# 37V_efuse.net
KiCad netlist of a schematic drawn in Altium Designer
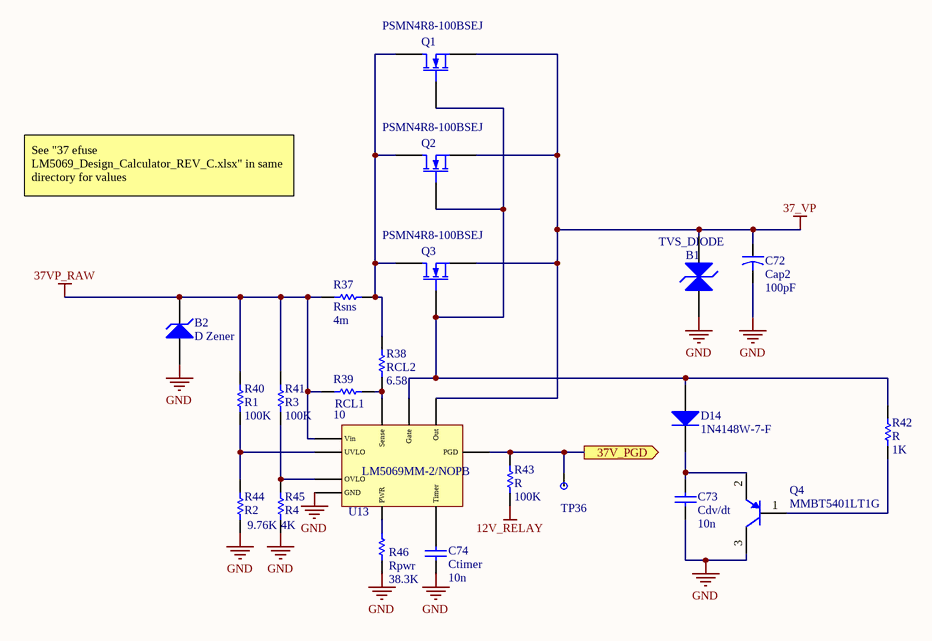
[diagram p0: 37V_efuse.SchDoc]

(export (version "E")
  (design (tool "Eeschema 10.0.6"))
  (components
    (comp (ref "B1")
      (value "TVS_DIODE")
      (footprint "SMBJ54A-13-F")
      (description "TVS Diode")
      (fields (field (name "PUBLISHER") "Altium Limited"))
      (libsource (lib "RSX_Diodes") (part "TVS_DIODE"))
    )
    (comp (ref "B2")
      (value "D Zener")
      (footprint "DIODE-0.7")
      (description "Zener Diode")
      (fields (field (name "PUBLISHER") "Altium Limited"))
      (libsource (lib "Miscellaneous Devices") (part "D Zener"))
    )
    (comp (ref "C72")
      (value "Cap2")
      (footprint "CAPR5-4X5")
      (description "Capacitor")
      (fields (field (name "ALTIUM_VALUE") "100pF") (field (name "PUBLISHER") "Altium Limited"))
      (libsource (lib "Miscellaneous Devices") (part "Cap2"))
    )
    (comp (ref "C73")
      (value "Cdv/dt")
      (footprint "RAD-0.3")
      (description "Capacitor")
      (fields (field (name "ALTIUM_VALUE") "10n") (field (name "PUBLISHER") "Altium Limited"))
      (libsource (lib "Miscellaneous Devices") (part "Cap"))
    )
    (comp (ref "C74")
      (value "Ctimer")
      (footprint "RAD-0.3")
      (description "Capacitor")
      (fields (field (name "ALTIUM_VALUE") "10n") (field (name "PUBLISHER") "Altium Limited"))
      (libsource (lib "Miscellaneous Devices") (part "Cap"))
    )
    (comp (ref "D14")
      (value "1N4148W-7-F")
      (footprint "DIOD-SOD123-2_V")
      (description "Fast Switching Diode, 100 V, 0.15 A, -65 to 150 degC, 2-Pin?SOD123, RoHS, Tape and Reel")
      (fields (field (name "MANUFACTURER") "DiodesIncorporated"))
      (libsource (lib "Altium Content Vault") (part "D-AK-2"))
    )
    (comp (ref "Q1")
      (value "PSMN4R8-100BSEJ")
      (footprint "DPAK254P1420X457-3N")
      (description "N-Channel MOSFET")
      (fields (field (name "PUBLISHER") "Altium Limited"))
      (libsource (lib "RSX_ICs") (part "PSMN4R8-100BSEJ"))
    )
    (comp (ref "Q2")
      (value "PSMN4R8-100BSEJ")
      (footprint "DPAK254P1420X457-3N")
      (description "N-Channel MOSFET")
      (fields (field (name "PUBLISHER") "Altium Limited"))
      (libsource (lib "RSX_ICs") (part "PSMN4R8-100BSEJ"))
    )
    (comp (ref "Q3")
      (value "PSMN4R8-100BSEJ")
      (footprint "DPAK254P1420X457-3N")
      (description "N-Channel MOSFET")
      (fields (field (name "PUBLISHER") "Altium Limited"))
      (libsource (lib "RSX_ICs") (part "PSMN4R8-100BSEJ"))
    )
    (comp (ref "Q4")
      (value "MMBT5401LT1G")
      (footprint "ONSC-SOT-23-3-318-08_V")
      (description "High Voltage Transistor, PNP Silicon, 3-Pin SOT-23, Pb-Free, Tape and Reel")
      (fields (field (name "MANUFACTURER") "On Semiconductor"))
      (libsource (lib "Altium Content Vault") (part "ONSC-PNP-B1E2C3-3"))
    )
    (comp (ref "R37")
      (value "Rsns")
      (footprint "RESC1608X06N_0603")
      (description "Resistor")
      (fields (field (name "ALTIUM_VALUE") "4m") (field (name "PUBLISHER") "Altium Limited"))
      (libsource (lib "RSX_Resistors") (part "Res1"))
    )
    (comp (ref "R38")
      (value "RCL2")
      (footprint "RESC1608X06N_0603")
      (description "Resistor")
      (fields (field (name "ALTIUM_VALUE") "6.58") (field (name "PUBLISHER") "Altium Limited"))
      (libsource (lib "RSX_Resistors") (part "Res1"))
    )
    (comp (ref "R39")
      (value "RCL1")
      (footprint "RESC1608X06N_0603")
      (description "Resistor")
      (fields (field (name "ALTIUM_VALUE") "10") (field (name "PUBLISHER") "Altium Limited"))
      (libsource (lib "RSX_Resistors") (part "Res1"))
    )
    (comp (ref "R40")
      (value "R1")
      (footprint "RESC1608X06N_0603")
      (description "Resistor")
      (fields (field (name "ALTIUM_VALUE") "100K") (field (name "PUBLISHER") "Altium Limited"))
      (libsource (lib "RSX_Resistors") (part "Res1"))
    )
    (comp (ref "R41")
      (value "R3")
      (footprint "RESC1608X06N_0603")
      (description "Resistor")
      (fields (field (name "ALTIUM_VALUE") "100K") (field (name "PUBLISHER") "Altium Limited"))
      (libsource (lib "RSX_Resistors") (part "Res1"))
    )
    (comp (ref "R42")
      (value "R")
      (footprint "RESC1608X06N_0603")
      (description "Resistor")
      (fields (field (name "ALTIUM_VALUE") "1K") (field (name "PUBLISHER") "Altium Limited"))
      (libsource (lib "RSX_Resistors") (part "Res1"))
    )
    (comp (ref "R43")
      (value "R")
      (footprint "RESC1608X06N_0603")
      (description "Resistor")
      (fields (field (name "ALTIUM_VALUE") "100K") (field (name "PUBLISHER") "Altium Limited"))
      (libsource (lib "RSX_Resistors") (part "Res1"))
    )
    (comp (ref "R44")
      (value "R2")
      (footprint "RESC1608X06N_0603")
      (description "Resistor")
      (fields (field (name "ALTIUM_VALUE") "9.76K") (field (name "PUBLISHER") "Altium Limited"))
      (libsource (lib "RSX_Resistors") (part "Res1"))
    )
    (comp (ref "R45")
      (value "R4")
      (footprint "RESC1608X06N_0603")
      (description "Resistor")
      (fields (field (name "ALTIUM_VALUE") "4K") (field (name "PUBLISHER") "Altium Limited"))
      (libsource (lib "RSX_Resistors") (part "Res1"))
    )
    (comp (ref "R46")
      (value "Rpwr")
      (footprint "RESC1608X06N_0603")
      (description "Resistor")
      (fields (field (name "ALTIUM_VALUE") "38.3K") (field (name "PUBLISHER") "Altium Limited"))
      (libsource (lib "RSX_Resistors") (part "Res1"))
    )
    (comp (ref "TP36")
      (value "TestPt")
      (footprint "50_MIL_PAD")
      (libsource (lib "RSX_Test_Points") (part "TestPt"))
    )
    (comp (ref "U13")
      (value "LM5069MM-2/NOPB")
      (footprint "TSSOP50P490X110-10N")
      (description "Hot Swap Controller 1-CH 80V N-Channel Positive High Voltage 10-Pin VSSOP T/R")
      (libsource (lib "RSX_ICs") (part "LM5069MM-2/NOPB"))
    )
  )
  (nets
    (net (code "1") (name "/37V_PGD") (class "Default")
      (node (ref "R43") (pin "2") (pinfunction "2_2") (pintype "passive"))
      (node (ref "TP36") (pin "1") (pinfunction "1_1") (pintype "passive"))
      (node (ref "U13") (pin "8") (pinfunction "PGD_8") (pintype "passive"))
    )
    (net (code "2") (name "12V_RELAY") (class "Default")
      (node (ref "R43") (pin "1") (pinfunction "1_1") (pintype "passive"))
    )
    (net (code "3") (name "37VP_RAW") (class "Default")
      (node (ref "B2") (pin "2") (pinfunction "K_2") (pintype "passive"))
      (node (ref "R37") (pin "1") (pinfunction "1_1") (pintype "passive"))
      (node (ref "R39") (pin "1") (pinfunction "1_1") (pintype "passive"))
      (node (ref "R40") (pin "2") (pinfunction "2_2") (pintype "passive"))
      (node (ref "R41") (pin "2") (pinfunction "2_2") (pintype "passive"))
      (node (ref "U13") (pin "2") (pinfunction "Vin_2") (pintype "passive"))
    )
    (net (code "4") (name "37_VP") (class "Default")
      (node (ref "B1") (pin "2") (pinfunction "K_2") (pintype "passive"))
      (node (ref "C72") (pin "1") (pinfunction "1_1") (pintype "passive"))
      (node (ref "Q1") (pin "3") (pinfunction "S_3") (pintype "passive"))
      (node (ref "Q2") (pin "3") (pinfunction "S_3") (pintype "passive"))
      (node (ref "Q3") (pin "3") (pinfunction "S_3") (pintype "passive"))
      (node (ref "U13") (pin "9") (pinfunction "Out_9") (pintype "passive"))
    )
    (net (code "5") (name "GND") (class "Default")
      (node (ref "B1") (pin "1") (pinfunction "A_1") (pintype "passive"))
      (node (ref "B2") (pin "1") (pinfunction "A_1") (pintype "passive"))
      (node (ref "C72") (pin "2") (pinfunction "2_2") (pintype "passive"))
      (node (ref "C73") (pin "2") (pinfunction "2_2") (pintype "passive"))
      (node (ref "C74") (pin "1") (pinfunction "1_1") (pintype "passive"))
      (node (ref "Q4") (pin "3") (pinfunction "C_3") (pintype "passive"))
      (node (ref "R44") (pin "1") (pinfunction "1_1") (pintype "passive"))
      (node (ref "R45") (pin "1") (pinfunction "1_1") (pintype "passive"))
      (node (ref "R46") (pin "1") (pinfunction "1_1") (pintype "passive"))
      (node (ref "U13") (pin "5") (pinfunction "GND_5") (pintype "passive"))
    )
    (net (code "6") (name "Net-(D14-A)") (class "Default")
      (node (ref "D14") (pin "1") (pinfunction "A_1") (pintype "passive"))
      (node (ref "Q1") (pin "1") (pinfunction "G_1") (pintype "passive"))
      (node (ref "Q2") (pin "1") (pinfunction "G_1") (pintype "passive"))
      (node (ref "Q3") (pin "1") (pinfunction "G_1") (pintype "passive"))
      (node (ref "R42") (pin "2") (pinfunction "2_2") (pintype "passive"))
      (node (ref "U13") (pin "10") (pinfunction "Gate_10") (pintype "passive"))
    )
    (net (code "7") (name "Net-(D14-K)") (class "Default")
      (node (ref "C73") (pin "1") (pinfunction "1_1") (pintype "passive"))
      (node (ref "D14") (pin "2") (pinfunction "K_2") (pintype "passive"))
      (node (ref "Q4") (pin "2") (pinfunction "E_2") (pintype "passive"))
    )
    (net (code "8") (name "Net-(Q1-D)") (class "Default")
      (node (ref "Q1") (pin "2") (pinfunction "D_2") (pintype "passive"))
      (node (ref "Q2") (pin "2") (pinfunction "D_2") (pintype "passive"))
      (node (ref "Q3") (pin "2") (pinfunction "D_2") (pintype "passive"))
      (node (ref "R37") (pin "2") (pinfunction "2_2") (pintype "passive"))
      (node (ref "R38") (pin "2") (pinfunction "2_2") (pintype "passive"))
    )
    (net (code "9") (name "Net-(Q4-B)") (class "Default")
      (node (ref "Q4") (pin "1") (pinfunction "B_1") (pintype "passive"))
      (node (ref "R42") (pin "1") (pinfunction "1_1") (pintype "passive"))
    )
    (net (code "10") (name "Net-(U13-OVLO)") (class "Default")
      (node (ref "R41") (pin "1") (pinfunction "1_1") (pintype "passive"))
      (node (ref "R45") (pin "2") (pinfunction "2_2") (pintype "passive"))
      (node (ref "U13") (pin "4") (pinfunction "OVLO_4") (pintype "passive"))
    )
    (net (code "11") (name "Net-(U13-PWR)") (class "Default")
      (node (ref "R46") (pin "2") (pinfunction "2_2") (pintype "passive"))
      (node (ref "U13") (pin "7") (pinfunction "PWR_7") (pintype "passive"))
    )
    (net (code "12") (name "Net-(U13-Sense)") (class "Default")
      (node (ref "R38") (pin "1") (pinfunction "1_1") (pintype "passive"))
      (node (ref "R39") (pin "2") (pinfunction "2_2") (pintype "passive"))
      (node (ref "U13") (pin "1") (pinfunction "Sense_1") (pintype "passive"))
    )
    (net (code "13") (name "Net-(U13-Timer)") (class "Default")
      (node (ref "C74") (pin "2") (pinfunction "2_2") (pintype "passive"))
      (node (ref "U13") (pin "6") (pinfunction "Timer_6") (pintype "passive"))
    )
    (net (code "14") (name "Net-(U13-UVLO)") (class "Default")
      (node (ref "R40") (pin "1") (pinfunction "1_1") (pintype "passive"))
      (node (ref "R44") (pin "2") (pinfunction "2_2") (pintype "passive"))
      (node (ref "U13") (pin "3") (pinfunction "UVLO_3") (pintype "passive"))
    )
  )
)
